# Fraduino.net
KiCad netlist of a schematic drawn in Altium Designer
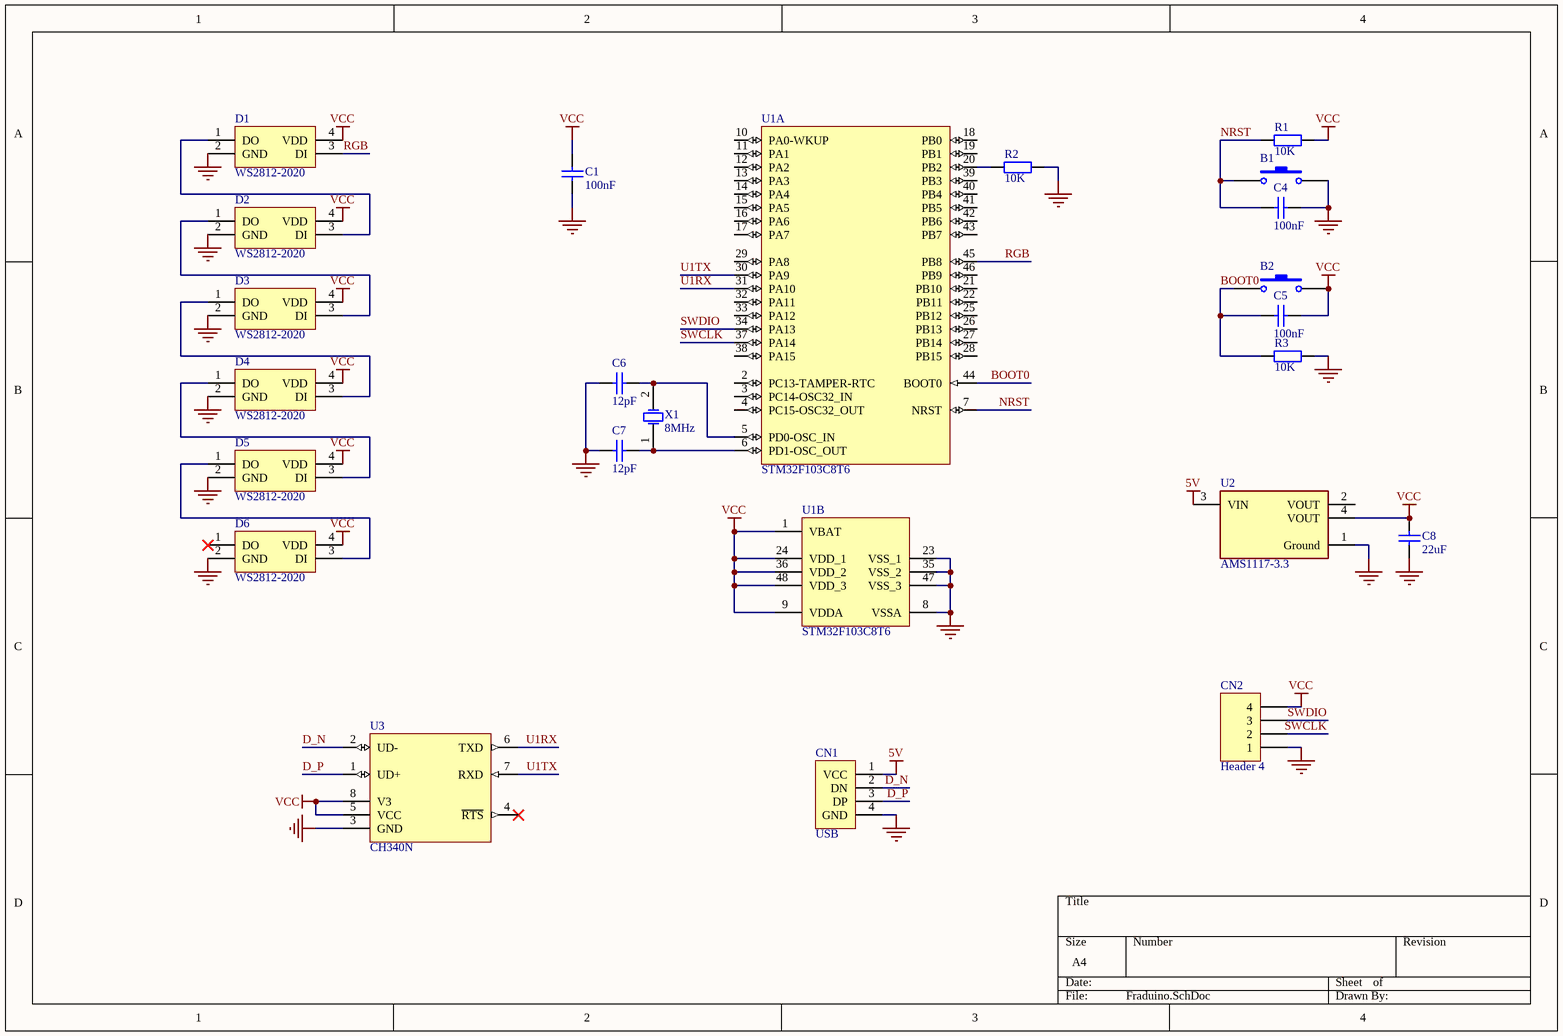
[diagram p0: Fraduino.SchDoc]

(export (version "E")
  (design (tool "Eeschema 10.0.6"))
  (components
    (comp (ref "B1")
      (value "SW-PB")
      (footprint "TSW SMD-3*4*2.5")
      (description "Switch")
      (fields (field (name "PUBLISHER") "Altium Limited"))
      (libsource (lib "Miscellaneous Devices") (part "SW-PB"))
    )
    (comp (ref "B2")
      (value "SW-PB")
      (footprint "TSW SMD-3*4*2.5")
      (description "Switch")
      (fields (field (name "PUBLISHER") "Altium Limited"))
      (libsource (lib "Miscellaneous Devices") (part "SW-PB"))
    )
    (comp (ref "C1")
      (value "100nF")
      (footprint "C0603")
      (description "Capacitor")
      (fields (field (name "Comment") "Cap") (field (name "PUBLISHER") "Altium Limited"))
      (libsource (lib "Miscellaneous Devices") (part "Cap"))
    )
    (comp (ref "C4")
      (value "100nF")
      (footprint "C0603")
      (description "Capacitor")
      (fields (field (name "Comment") "Cap") (field (name "PUBLISHER") "Altium Limited"))
      (libsource (lib "Miscellaneous Devices") (part "Cap"))
    )
    (comp (ref "C5")
      (value "100nF")
      (footprint "C0603")
      (description "Capacitor")
      (fields (field (name "Comment") "Cap") (field (name "PUBLISHER") "Altium Limited"))
      (libsource (lib "Miscellaneous Devices") (part "Cap"))
    )
    (comp (ref "C6")
      (value "12pF")
      (footprint "C0603")
      (description "Capacitor")
      (fields (field (name "Comment") "Cap") (field (name "PUBLISHER") "Altium Limited"))
      (libsource (lib "Miscellaneous Devices") (part "Cap"))
    )
    (comp (ref "C7")
      (value "12pF")
      (footprint "C0603")
      (description "Capacitor")
      (fields (field (name "Comment") "Cap") (field (name "PUBLISHER") "Altium Limited"))
      (libsource (lib "Miscellaneous Devices") (part "Cap"))
    )
    (comp (ref "C8")
      (value "22uF")
      (footprint "C0603")
      (description "Capacitor")
      (fields (field (name "Comment") "Cap") (field (name "PUBLISHER") "Altium Limited"))
      (libsource (lib "Miscellaneous Devices") (part "Cap"))
    )
    (comp (ref "CN1")
      (value "USB")
      (footprint "USB_SMD")
      (description "USB公头")
      (libsource (lib "接口类") (part "USB-SMD"))
    )
    (comp (ref "CN2")
      (value "Header 4")
      (footprint "TESTPAD4")
      (description "Header, 4-Pin")
      (fields (field (name "PUBLISHER") "Altium Limited"))
      (libsource (lib "Miscellaneous Connectors") (part "Header 4"))
    )
    (comp (ref "D1")
      (value "WS2812-2020")
      (footprint "WS2812-2020-S")
      (description "RGB LED")
      (libsource (lib "LED") (part "WS2812-2020"))
    )
    (comp (ref "D2")
      (value "WS2812-2020")
      (footprint "WS2812-2020-S")
      (description "RGB LED")
      (libsource (lib "LED") (part "WS2812-2020"))
    )
    (comp (ref "D3")
      (value "WS2812-2020")
      (footprint "WS2812-2020-S")
      (description "RGB LED")
      (libsource (lib "LED") (part "WS2812-2020"))
    )
    (comp (ref "D4")
      (value "WS2812-2020")
      (footprint "WS2812-2020-S")
      (description "RGB LED")
      (libsource (lib "LED") (part "WS2812-2020"))
    )
    (comp (ref "D5")
      (value "WS2812-2020")
      (footprint "WS2812-2020-S")
      (description "RGB LED")
      (libsource (lib "LED") (part "WS2812-2020"))
    )
    (comp (ref "D6")
      (value "WS2812-2020")
      (footprint "WS2812-2020-S")
      (description "RGB LED")
      (libsource (lib "LED") (part "WS2812-2020"))
    )
    (comp (ref "R1")
      (value "10K")
      (footprint "R0603")
      (description "Resistor")
      (fields (field (name "Comment") "Res2") (field (name "PUBLISHER") "Altium Limited"))
      (libsource (lib "") (part "Res2_1"))
    )
    (comp (ref "R2")
      (value "10K")
      (footprint "R0603")
      (description "Resistor")
      (fields (field (name "Comment") "Res2") (field (name "PUBLISHER") "Altium Limited"))
      (libsource (lib "") (part "Res2_1"))
    )
    (comp (ref "R3")
      (value "10K")
      (footprint "R0603")
      (description "Resistor")
      (fields (field (name "Comment") "Res2") (field (name "PUBLISHER") "Altium Limited"))
      (libsource (lib "Miscellaneous Devices") (part "Res2"))
    )
    (comp (ref "U1")
      (value "STM32F103C8T6")
      (footprint "STM-LQFP48_L")
      (libsource (lib "Altium Content Vault") (part "MC-ARM-STM32F103X8_B-SQ48"))
    )
    (comp (ref "U2")
      (value "AMS1117-3.3")
      (footprint "FP-AMS1117-IPC_C")
      (description "LDO Voltage Regulators 1A, 3.3V")
      (fields
        (field (name "OCTOPART") "https://octopart.com/ams1117-3.3-advanced+monolithic+systems-25899300")
        (field (name "MANUFACTURER") "Advanced Monolithic Systems")
      )
      (libsource (lib "Altium Content Vault") (part "8bdbb5f8e77002000e30dd2845d0354"))
    )
    (comp (ref "U3")
      (value "CH340N")
      (footprint "SOP8_L")
      (description "串口转USB")
      (libsource (lib "IC芯片") (part "CH340N"))
    )
    (comp (ref "X1")
      (value "8MHz")
      (footprint "ABRA-ABM3-2_V")
      (description "Miniature Ceramic Crystal, 8 MHz, -40 to 85 degC, 2-Pin SMD, RoHS, Tape and Reel")
      (fields (field (name "MANUFACTURER") "ABRACON") (field (name "TOLERANCE") "20PPM"))
      (libsource (lib "Altium Content Vault") (part "XTAL_1-2-2"))
    )
  )
  (nets
    (net (code "1") (name "/BOOT0") (class "Default")
      (node (ref "B2") (pin "1") (pinfunction "1_1") (pintype "passive"))
      (node (ref "C5") (pin "2") (pinfunction "2_2") (pintype "passive"))
      (node (ref "R3") (pin "2") (pinfunction "2_2") (pintype "passive"))
      (node (ref "U1") (pin "44") (pinfunction "BOOT0_44") (pintype "input"))
    )
    (net (code "2") (name "/D_N") (class "Default")
      (node (ref "CN1") (pin "2") (pinfunction "DN_2") (pintype "passive"))
      (node (ref "U3") (pin "2") (pinfunction "UD-_2") (pintype "bidirectional"))
    )
    (net (code "3") (name "/D_P") (class "Default")
      (node (ref "CN1") (pin "3") (pinfunction "DP_3") (pintype "passive"))
      (node (ref "U3") (pin "1") (pinfunction "UD+_1") (pintype "bidirectional"))
    )
    (net (code "4") (name "/NRST") (class "Default")
      (node (ref "B1") (pin "1") (pinfunction "1_1") (pintype "passive"))
      (node (ref "C4") (pin "2") (pinfunction "2_2") (pintype "passive"))
      (node (ref "R1") (pin "2") (pinfunction "2_2") (pintype "passive"))
      (node (ref "U1") (pin "7") (pinfunction "NRST_7") (pintype "bidirectional"))
    )
    (net (code "5") (name "/RGB") (class "Default")
      (node (ref "D1") (pin "3") (pinfunction "DI_3") (pintype "passive"))
      (node (ref "U1") (pin "45") (pinfunction "PB8_45") (pintype "bidirectional"))
    )
    (net (code "6") (name "/SWCLK") (class "Default")
      (node (ref "CN2") (pin "2") (pinfunction "2_2") (pintype "passive"))
      (node (ref "U1") (pin "37") (pinfunction "PA14_37") (pintype "bidirectional"))
    )
    (net (code "7") (name "/SWDIO") (class "Default")
      (node (ref "CN2") (pin "3") (pinfunction "3_3") (pintype "passive"))
      (node (ref "U1") (pin "34") (pinfunction "PA13_34") (pintype "bidirectional"))
    )
    (net (code "8") (name "/U1RX") (class "Default")
      (node (ref "U1") (pin "31") (pinfunction "PA10_31") (pintype "bidirectional"))
      (node (ref "U3") (pin "6") (pinfunction "TXD_6") (pintype "output"))
    )
    (net (code "9") (name "/U1TX") (class "Default")
      (node (ref "U1") (pin "30") (pinfunction "PA9_30") (pintype "bidirectional"))
      (node (ref "U3") (pin "7") (pinfunction "RXD_7") (pintype "input"))
    )
    (net (code "10") (name "5V") (class "Default")
      (node (ref "CN1") (pin "1") (pinfunction "VCC_1") (pintype "passive"))
      (node (ref "U2") (pin "3") (pinfunction "VIN_3") (pintype "power_in"))
    )
    (net (code "11") (name "GND") (class "Default")
      (node (ref "B1") (pin "2") (pinfunction "2_2") (pintype "passive"))
      (node (ref "C1") (pin "1") (pinfunction "1_1") (pintype "passive"))
      (node (ref "C4") (pin "1") (pinfunction "1_1") (pintype "passive"))
      (node (ref "C6") (pin "2") (pinfunction "2_2") (pintype "passive"))
      (node (ref "C7") (pin "2") (pinfunction "2_2") (pintype "passive"))
      (node (ref "C8") (pin "2") (pinfunction "2_2") (pintype "passive"))
      (node (ref "CN1") (pin "4") (pinfunction "GND_4") (pintype "passive"))
      (node (ref "CN2") (pin "1") (pinfunction "1_1") (pintype "passive"))
      (node (ref "D1") (pin "2") (pinfunction "GND_2") (pintype "passive"))
      (node (ref "D2") (pin "2") (pinfunction "GND_2") (pintype "passive"))
      (node (ref "D3") (pin "2") (pinfunction "GND_2") (pintype "passive"))
      (node (ref "D4") (pin "2") (pinfunction "GND_2") (pintype "passive"))
      (node (ref "D5") (pin "2") (pinfunction "GND_2") (pintype "passive"))
      (node (ref "D6") (pin "2") (pinfunction "GND_2") (pintype "passive"))
      (node (ref "R2") (pin "1") (pinfunction "1_1") (pintype "passive"))
      (node (ref "R3") (pin "1") (pinfunction "1_1") (pintype "passive"))
      (node (ref "U1") (pin "23") (pinfunction "VSS_1_23") (pintype "power_in"))
      (node (ref "U1") (pin "35") (pinfunction "VSS_2_35") (pintype "power_in"))
      (node (ref "U1") (pin "47") (pinfunction "VSS_3_47") (pintype "power_in"))
      (node (ref "U1") (pin "8") (pinfunction "VSSA_8") (pintype "power_in"))
      (node (ref "U2") (pin "1") (pinfunction "Ground_1") (pintype "power_in"))
      (node (ref "U3") (pin "3") (pinfunction "GND_3") (pintype "power_in"))
    )
    (net (code "12") (name "Net-(D1-DO)") (class "Default")
      (node (ref "D1") (pin "1") (pinfunction "DO_1") (pintype "passive"))
      (node (ref "D2") (pin "3") (pinfunction "DI_3") (pintype "passive"))
    )
    (net (code "13") (name "Net-(D2-DO)") (class "Default")
      (node (ref "D2") (pin "1") (pinfunction "DO_1") (pintype "passive"))
      (node (ref "D3") (pin "3") (pinfunction "DI_3") (pintype "passive"))
    )
    (net (code "14") (name "Net-(D3-DO)") (class "Default")
      (node (ref "D3") (pin "1") (pinfunction "DO_1") (pintype "passive"))
      (node (ref "D4") (pin "3") (pinfunction "DI_3") (pintype "passive"))
    )
    (net (code "15") (name "Net-(D4-DO)") (class "Default")
      (node (ref "D4") (pin "1") (pinfunction "DO_1") (pintype "passive"))
      (node (ref "D5") (pin "3") (pinfunction "DI_3") (pintype "passive"))
    )
    (net (code "16") (name "Net-(D5-DO)") (class "Default")
      (node (ref "D5") (pin "1") (pinfunction "DO_1") (pintype "passive"))
      (node (ref "D6") (pin "3") (pinfunction "DI_3") (pintype "passive"))
    )
    (net (code "17") (name "Net-(U1A-PB2)") (class "Default")
      (node (ref "R2") (pin "2") (pinfunction "2_2") (pintype "passive"))
      (node (ref "U1") (pin "20") (pinfunction "PB2_20") (pintype "bidirectional"))
    )
    (net (code "18") (name "Net-(U1A-PD0-OSC_IN)") (class "Default")
      (node (ref "C6") (pin "1") (pinfunction "1_1") (pintype "passive"))
      (node (ref "U1") (pin "5") (pinfunction "PD0-OSC_IN_5") (pintype "bidirectional"))
      (node (ref "X1") (pin "2") (pinfunction "X2_2") (pintype "passive"))
    )
    (net (code "19") (name "Net-(U1A-PD1-OSC_OUT)") (class "Default")
      (node (ref "C7") (pin "1") (pinfunction "1_1") (pintype "passive"))
      (node (ref "U1") (pin "6") (pinfunction "PD1-OSC_OUT_6") (pintype "bidirectional"))
      (node (ref "X1") (pin "1") (pinfunction "X1_1") (pintype "passive"))
    )
    (net (code "20") (name "VCC") (class "Default")
      (node (ref "B2") (pin "2") (pinfunction "2_2") (pintype "passive"))
      (node (ref "C1") (pin "2") (pinfunction "2_2") (pintype "passive"))
      (node (ref "C5") (pin "1") (pinfunction "1_1") (pintype "passive"))
      (node (ref "C8") (pin "1") (pinfunction "1_1") (pintype "passive"))
      (node (ref "CN2") (pin "4") (pinfunction "4_4") (pintype "passive"))
      (node (ref "D1") (pin "4") (pinfunction "VDD_4") (pintype "passive"))
      (node (ref "D2") (pin "4") (pinfunction "VDD_4") (pintype "passive"))
      (node (ref "D3") (pin "4") (pinfunction "VDD_4") (pintype "passive"))
      (node (ref "D4") (pin "4") (pinfunction "VDD_4") (pintype "passive"))
      (node (ref "D5") (pin "4") (pinfunction "VDD_4") (pintype "passive"))
      (node (ref "D6") (pin "4") (pinfunction "VDD_4") (pintype "passive"))
      (node (ref "R1") (pin "1") (pinfunction "1_1") (pintype "passive"))
      (node (ref "U1") (pin "1") (pinfunction "VBAT_1") (pintype "power_in"))
      (node (ref "U1") (pin "24") (pinfunction "VDD_1_24") (pintype "power_in"))
      (node (ref "U1") (pin "36") (pinfunction "VDD_2_36") (pintype "power_in"))
      (node (ref "U1") (pin "48") (pinfunction "VDD_3_48") (pintype "power_in"))
      (node (ref "U1") (pin "9") (pinfunction "VDDA_9") (pintype "power_in"))
      (node (ref "U2") (pin "4") (pinfunction "VOUT_4") (pintype "passive"))
      (node (ref "U3") (pin "5") (pinfunction "VCC_5") (pintype "power_in"))
      (node (ref "U3") (pin "8") (pinfunction "V3_8") (pintype "power_in"))
    )
    (net (code "21") (name "unconnected-(D6-DO-Pad1)") (class "Default")
      (node (ref "D6") (pin "1") (pinfunction "DO_1") (pintype "passive+no_connect"))
    )
    (net (code "22") (name "unconnected-(U1A-PA0-WKUP-Pad10)") (class "Default")
      (node (ref "U1") (pin "10") (pinfunction "PA0-WKUP_10") (pintype "bidirectional"))
    )
    (net (code "23") (name "unconnected-(U1A-PA1-Pad11)") (class "Default")
      (node (ref "U1") (pin "11") (pinfunction "PA1_11") (pintype "bidirectional"))
    )
    (net (code "24") (name "unconnected-(U1A-PA2-Pad12)") (class "Default")
      (node (ref "U1") (pin "12") (pinfunction "PA2_12") (pintype "bidirectional"))
    )
    (net (code "25") (name "unconnected-(U1A-PA3-Pad13)") (class "Default")
      (node (ref "U1") (pin "13") (pinfunction "PA3_13") (pintype "bidirectional"))
    )
    (net (code "26") (name "unconnected-(U1A-PA4-Pad14)") (class "Default")
      (node (ref "U1") (pin "14") (pinfunction "PA4_14") (pintype "bidirectional"))
    )
    (net (code "27") (name "unconnected-(U1A-PA5-Pad15)") (class "Default")
      (node (ref "U1") (pin "15") (pinfunction "PA5_15") (pintype "bidirectional"))
    )
    (net (code "28") (name "unconnected-(U1A-PA6-Pad16)") (class "Default")
      (node (ref "U1") (pin "16") (pinfunction "PA6_16") (pintype "bidirectional"))
    )
    (net (code "29") (name "unconnected-(U1A-PA7-Pad17)") (class "Default")
      (node (ref "U1") (pin "17") (pinfunction "PA7_17") (pintype "bidirectional"))
    )
    (net (code "30") (name "unconnected-(U1A-PA8-Pad29)") (class "Default")
      (node (ref "U1") (pin "29") (pinfunction "PA8_29") (pintype "bidirectional"))
    )
    (net (code "31") (name "unconnected-(U1A-PA11-Pad32)") (class "Default")
      (node (ref "U1") (pin "32") (pinfunction "PA11_32") (pintype "bidirectional"))
    )
    (net (code "32") (name "unconnected-(U1A-PA12-Pad33)") (class "Default")
      (node (ref "U1") (pin "33") (pinfunction "PA12_33") (pintype "bidirectional"))
    )
    (net (code "33") (name "unconnected-(U1A-PA15-Pad38)") (class "Default")
      (node (ref "U1") (pin "38") (pinfunction "PA15_38") (pintype "bidirectional"))
    )
    (net (code "34") (name "unconnected-(U1A-PB0-Pad18)") (class "Default")
      (node (ref "U1") (pin "18") (pinfunction "PB0_18") (pintype "bidirectional"))
    )
    (net (code "35") (name "unconnected-(U1A-PB1-Pad19)") (class "Default")
      (node (ref "U1") (pin "19") (pinfunction "PB1_19") (pintype "bidirectional"))
    )
    (net (code "36") (name "unconnected-(U1A-PB3-Pad39)") (class "Default")
      (node (ref "U1") (pin "39") (pinfunction "PB3_39") (pintype "bidirectional"))
    )
    (net (code "37") (name "unconnected-(U1A-PB4-Pad40)") (class "Default")
      (node (ref "U1") (pin "40") (pinfunction "PB4_40") (pintype "bidirectional"))
    )
    (net (code "38") (name "unconnected-(U1A-PB5-Pad41)") (class "Default")
      (node (ref "U1") (pin "41") (pinfunction "PB5_41") (pintype "bidirectional"))
    )
    (net (code "39") (name "unconnected-(U1A-PB6-Pad42)") (class "Default")
      (node (ref "U1") (pin "42") (pinfunction "PB6_42") (pintype "bidirectional"))
    )
    (net (code "40") (name "unconnected-(U1A-PB7-Pad43)") (class "Default")
      (node (ref "U1") (pin "43") (pinfunction "PB7_43") (pintype "bidirectional"))
    )
    (net (code "41") (name "unconnected-(U1A-PB9-Pad46)") (class "Default")
      (node (ref "U1") (pin "46") (pinfunction "PB9_46") (pintype "bidirectional"))
    )
    (net (code "42") (name "unconnected-(U1A-PB10-Pad21)") (class "Default")
      (node (ref "U1") (pin "21") (pinfunction "PB10_21") (pintype "bidirectional"))
    )
    (net (code "43") (name "unconnected-(U1A-PB11-Pad22)") (class "Default")
      (node (ref "U1") (pin "22") (pinfunction "PB11_22") (pintype "bidirectional"))
    )
    (net (code "44") (name "unconnected-(U1A-PB12-Pad25)") (class "Default")
      (node (ref "U1") (pin "25") (pinfunction "PB12_25") (pintype "bidirectional"))
    )
    (net (code "45") (name "unconnected-(U1A-PB13-Pad26)") (class "Default")
      (node (ref "U1") (pin "26") (pinfunction "PB13_26") (pintype "bidirectional"))
    )
    (net (code "46") (name "unconnected-(U1A-PB14-Pad27)") (class "Default")
      (node (ref "U1") (pin "27") (pinfunction "PB14_27") (pintype "bidirectional"))
    )
    (net (code "47") (name "unconnected-(U1A-PB15-Pad28)") (class "Default")
      (node (ref "U1") (pin "28") (pinfunction "PB15_28") (pintype "bidirectional"))
    )
    (net (code "48") (name "unconnected-(U1A-PC13-TAMPER-RTC-Pad2)") (class "Default")
      (node (ref "U1") (pin "2") (pinfunction "PC13-TAMPER-RTC_2") (pintype "bidirectional"))
    )
    (net (code "49") (name "unconnected-(U1A-PC14-OSC32_IN-Pad3)") (class "Default")
      (node (ref "U1") (pin "3") (pinfunction "PC14-OSC32_IN_3") (pintype "bidirectional"))
    )
    (net (code "50") (name "unconnected-(U1A-PC15-OSC32_OUT-Pad4)") (class "Default")
      (node (ref "U1") (pin "4") (pinfunction "PC15-OSC32_OUT_4") (pintype "bidirectional"))
    )
    (net (code "51") (name "unconnected-(U2-VOUT-Pad2)") (class "Default")
      (node (ref "U2") (pin "2") (pinfunction "VOUT_2") (pintype "passive"))
    )
    (net (code "52") (name "unconnected-(U3-~{RTS}-Pad4)") (class "Default")
      (node (ref "U3") (pin "4") (pinfunction "~{RTS}_4") (pintype "output+no_connect"))
    )
  )
)
